# sousvide.net
KiCad netlist of a schematic drawn in EAGLE
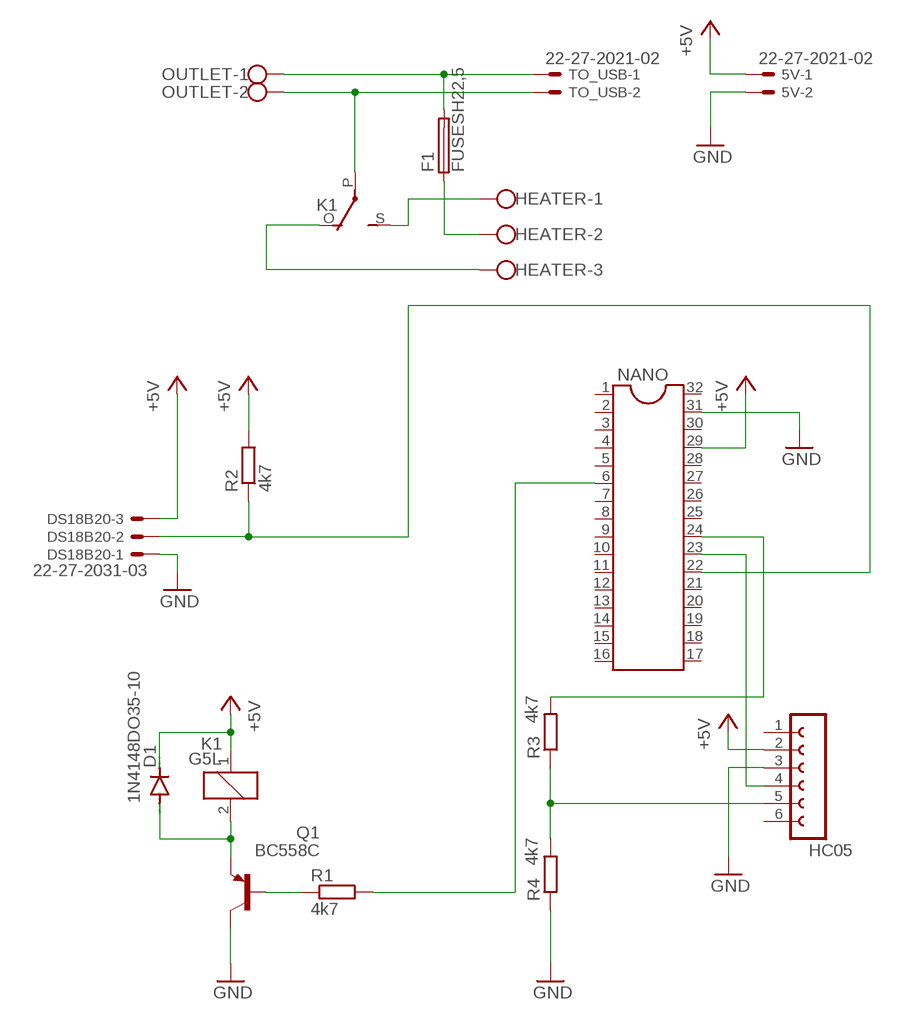
[diagram p0: schematic, sheet 1]

(export (version "E")
  (design (tool "Eeschema 10.0.6"))
  (components
    (comp (ref "5V")
      (value "22-27-2021-02")
      (footprint "eagle-import:6410-02")
      (fields (field (name "MF") "MOLEX"))
      (libsource (lib "eagle-import") (part "22-?-0227-2021"))
    )
    (comp (ref "D1")
      (value "1N4148DO35-10")
      (footprint "eagle-import:DO35-10")
      (libsource (lib "eagle-import") (part "1N4148DO35-10"))
    )
    (comp (ref "DS18B20")
      (value "22-27-2031-03")
      (footprint "eagle-import:6410-03")
      (fields (field (name "MF") "MOLEX"))
      (libsource (lib "eagle-import") (part "22-?-0327-2031"))
    )
    (comp (ref "F1")
      (value "FUSESH22,5")
      (footprint "eagle-import:SH22,5")
      (libsource (lib "eagle-import") (part "FUSESH22,5"))
    )
    (comp (ref "HC05")
      (value "FE06-1")
      (footprint "eagle-import:FE06")
      (libsource (lib "eagle-import") (part "FE06-1"))
    )
    (comp (ref "HEATER")
      (value "W237-103")
      (footprint "eagle-import:W237-103")
      (fields (field (name "MPN") "237-103"))
      (libsource (lib "eagle-import") (part "W237-103"))
    )
    (comp (ref "K1")
      (value "G5L")
      (footprint "eagle-import:G5LE")
      (libsource (lib "eagle-import") (part "G5L"))
    )
    (comp (ref "NANO")
      (value "DIL32")
      (footprint "eagle-import:DIL32")
      (libsource (lib "eagle-import") (part "DIL32"))
    )
    (comp (ref "OUTLET")
      (value "W237-102")
      (footprint "eagle-import:W237-102")
      (fields (field (name "MPN") "237-102"))
      (libsource (lib "eagle-import") (part "W237-102"))
    )
    (comp (ref "Q1")
      (value "BC558C")
      (footprint "eagle-import:TO92-EBC")
      (libsource (lib "eagle-import") (part "BC558C"))
    )
    (comp (ref "R1")
      (value "4k7")
      (footprint "eagle-import:0204_7")
      (libsource (lib "eagle-import") (part "R-EU_0204/7"))
    )
    (comp (ref "R2")
      (value "4k7")
      (footprint "eagle-import:0204_7")
      (libsource (lib "eagle-import") (part "R-EU_0204/7"))
    )
    (comp (ref "R3")
      (value "4k7")
      (footprint "eagle-import:0204_7")
      (libsource (lib "eagle-import") (part "R-EU_0204/7"))
    )
    (comp (ref "R4")
      (value "4k7")
      (footprint "eagle-import:0204_7")
      (libsource (lib "eagle-import") (part "R-EU_0204/7"))
    )
    (comp (ref "TO_USB")
      (value "22-27-2021-02")
      (footprint "eagle-import:6410-02")
      (fields (field (name "MF") "MOLEX"))
      (libsource (lib "eagle-import") (part "22-?-0227-2021"))
    )
  )
  (nets
    (net (code "1") (name "+5V") (class "Default")
      (node (ref "5V") (pin "1") (pinfunction "S_1") (pintype "passive"))
      (node (ref "D1") (pin "C") (pinfunction "C_C") (pintype "passive"))
      (node (ref "DS18B20") (pin "3") (pinfunction "S_3") (pintype "passive"))
      (node (ref "HC05") (pin "2") (pinfunction "2_2") (pintype "passive"))
      (node (ref "K1") (pin "1") (pinfunction "1_1") (pintype "passive"))
      (node (ref "NANO") (pin "29") (pinfunction "29_29") (pintype "passive"))
      (node (ref "R2") (pin "2") (pinfunction "2_2") (pintype "passive"))
    )
    (net (code "2") (name "GND") (class "Default")
      (node (ref "5V") (pin "2") (pinfunction "S_2") (pintype "passive"))
      (node (ref "DS18B20") (pin "1") (pinfunction "S_1") (pintype "passive"))
      (node (ref "HC05") (pin "3") (pinfunction "3_3") (pintype "passive"))
      (node (ref "NANO") (pin "31") (pinfunction "31_31") (pintype "passive"))
      (node (ref "Q1") (pin "C") (pinfunction "C_C") (pintype "passive"))
      (node (ref "R4") (pin "1") (pinfunction "1_1") (pintype "passive"))
    )
    (net (code "3") (name "Net-(D1-PadA)") (class "Default")
      (node (ref "D1") (pin "A") (pinfunction "A_A") (pintype "passive"))
      (node (ref "K1") (pin "2") (pinfunction "2_2") (pintype "passive"))
      (node (ref "Q1") (pin "E") (pinfunction "E_E") (pintype "passive"))
    )
    (net (code "4") (name "Net-(DS18B20B-S)") (class "Default")
      (node (ref "DS18B20") (pin "2") (pinfunction "S_2") (pintype "passive"))
      (node (ref "NANO") (pin "22") (pinfunction "22_22") (pintype "passive"))
      (node (ref "R2") (pin "1") (pinfunction "1_1") (pintype "passive"))
    )
    (net (code "5") (name "Net-(HC05-Pad4)") (class "Default")
      (node (ref "HC05") (pin "4") (pinfunction "4_4") (pintype "passive"))
      (node (ref "NANO") (pin "23") (pinfunction "23_23") (pintype "passive"))
    )
    (net (code "6") (name "Net-(HC05-Pad5)") (class "Default")
      (node (ref "HC05") (pin "5") (pinfunction "5_5") (pintype "passive"))
      (node (ref "R3") (pin "1") (pinfunction "1_1") (pintype "passive"))
      (node (ref "R4") (pin "2") (pinfunction "2_2") (pintype "passive"))
    )
    (net (code "7") (name "Net-(HEATERA-KL)") (class "Default")
      (node (ref "HEATER") (pin "1") (pinfunction "KL_1") (pintype "passive"))
      (node (ref "K1") (pin "S") (pinfunction "S_S") (pintype "passive"))
    )
    (net (code "8") (name "Net-(HEATERB-KL)") (class "Default")
      (node (ref "F1") (pin "1") (pinfunction "1_1") (pintype "passive"))
      (node (ref "HEATER") (pin "2") (pinfunction "KL_2") (pintype "passive"))
    )
    (net (code "9") (name "Net-(HEATERC-KL)") (class "Default")
      (node (ref "HEATER") (pin "3") (pinfunction "KL_3") (pintype "passive"))
      (node (ref "K1") (pin "O") (pinfunction "O_O") (pintype "passive"))
    )
    (net (code "10") (name "Net-(NANO-Pad6)") (class "Default")
      (node (ref "NANO") (pin "6") (pinfunction "6_6") (pintype "passive"))
      (node (ref "R1") (pin "2") (pinfunction "2_2") (pintype "passive"))
    )
    (net (code "11") (name "Net-(NANO-Pad24)") (class "Default")
      (node (ref "NANO") (pin "24") (pinfunction "24_24") (pintype "passive"))
      (node (ref "R3") (pin "2") (pinfunction "2_2") (pintype "passive"))
    )
    (net (code "12") (name "Net-(OUTLETA-KL)") (class "Default")
      (node (ref "F1") (pin "2") (pinfunction "2_2") (pintype "passive"))
      (node (ref "OUTLET") (pin "1") (pinfunction "KL_1") (pintype "passive"))
      (node (ref "TO_USB") (pin "1") (pinfunction "S_1") (pintype "passive"))
    )
    (net (code "13") (name "Net-(OUTLETB-KL)") (class "Default")
      (node (ref "K1") (pin "P") (pinfunction "P_P") (pintype "passive"))
      (node (ref "OUTLET") (pin "2") (pinfunction "KL_2") (pintype "passive"))
      (node (ref "TO_USB") (pin "2") (pinfunction "S_2") (pintype "passive"))
    )
    (net (code "14") (name "Net-(Q1-PadB)") (class "Default")
      (node (ref "Q1") (pin "B") (pinfunction "B_B") (pintype "passive"))
      (node (ref "R1") (pin "1") (pinfunction "1_1") (pintype "passive"))
    )
    (net (code "15") (name "unconnected-(HC05-Pad1)") (class "Default")
      (node (ref "HC05") (pin "1") (pinfunction "1_1") (pintype "passive"))
    )
    (net (code "16") (name "unconnected-(HC05-Pad6)") (class "Default")
      (node (ref "HC05") (pin "6") (pinfunction "6_6") (pintype "passive"))
    )
    (net (code "17") (name "unconnected-(NANO-Pad1)") (class "Default")
      (node (ref "NANO") (pin "1") (pinfunction "1_1") (pintype "passive"))
    )
    (net (code "18") (name "unconnected-(NANO-Pad2)") (class "Default")
      (node (ref "NANO") (pin "2") (pinfunction "2_2") (pintype "passive"))
    )
    (net (code "19") (name "unconnected-(NANO-Pad3)") (class "Default")
      (node (ref "NANO") (pin "3") (pinfunction "3_3") (pintype "passive"))
    )
    (net (code "20") (name "unconnected-(NANO-Pad4)") (class "Default")
      (node (ref "NANO") (pin "4") (pinfunction "4_4") (pintype "passive"))
    )
    (net (code "21") (name "unconnected-(NANO-Pad5)") (class "Default")
      (node (ref "NANO") (pin "5") (pinfunction "5_5") (pintype "passive"))
    )
    (net (code "22") (name "unconnected-(NANO-Pad7)") (class "Default")
      (node (ref "NANO") (pin "7") (pinfunction "7_7") (pintype "passive"))
    )
    (net (code "23") (name "unconnected-(NANO-Pad8)") (class "Default")
      (node (ref "NANO") (pin "8") (pinfunction "8_8") (pintype "passive"))
    )
    (net (code "24") (name "unconnected-(NANO-Pad9)") (class "Default")
      (node (ref "NANO") (pin "9") (pinfunction "9_9") (pintype "passive"))
    )
    (net (code "25") (name "unconnected-(NANO-Pad10)") (class "Default")
      (node (ref "NANO") (pin "10") (pinfunction "10_10") (pintype "passive"))
    )
    (net (code "26") (name "unconnected-(NANO-Pad11)") (class "Default")
      (node (ref "NANO") (pin "11") (pinfunction "11_11") (pintype "passive"))
    )
    (net (code "27") (name "unconnected-(NANO-Pad12)") (class "Default")
      (node (ref "NANO") (pin "12") (pinfunction "12_12") (pintype "passive"))
    )
    (net (code "28") (name "unconnected-(NANO-Pad13)") (class "Default")
      (node (ref "NANO") (pin "13") (pinfunction "13_13") (pintype "passive"))
    )
    (net (code "29") (name "unconnected-(NANO-Pad14)") (class "Default")
      (node (ref "NANO") (pin "14") (pinfunction "14_14") (pintype "passive"))
    )
    (net (code "30") (name "unconnected-(NANO-Pad15)") (class "Default")
      (node (ref "NANO") (pin "15") (pinfunction "15_15") (pintype "passive"))
    )
    (net (code "31") (name "unconnected-(NANO-Pad16)") (class "Default")
      (node (ref "NANO") (pin "16") (pinfunction "16_16") (pintype "passive"))
    )
    (net (code "32") (name "unconnected-(NANO-Pad17)") (class "Default")
      (node (ref "NANO") (pin "17") (pinfunction "17_17") (pintype "passive"))
    )
    (net (code "33") (name "unconnected-(NANO-Pad18)") (class "Default")
      (node (ref "NANO") (pin "18") (pinfunction "18_18") (pintype "passive"))
    )
    (net (code "34") (name "unconnected-(NANO-Pad19)") (class "Default")
      (node (ref "NANO") (pin "19") (pinfunction "19_19") (pintype "passive"))
    )
    (net (code "35") (name "unconnected-(NANO-Pad20)") (class "Default")
      (node (ref "NANO") (pin "20") (pinfunction "20_20") (pintype "passive"))
    )
    (net (code "36") (name "unconnected-(NANO-Pad21)") (class "Default")
      (node (ref "NANO") (pin "21") (pinfunction "21_21") (pintype "passive"))
    )
    (net (code "37") (name "unconnected-(NANO-Pad25)") (class "Default")
      (node (ref "NANO") (pin "25") (pinfunction "25_25") (pintype "passive"))
    )
    (net (code "38") (name "unconnected-(NANO-Pad26)") (class "Default")
      (node (ref "NANO") (pin "26") (pinfunction "26_26") (pintype "passive"))
    )
    (net (code "39") (name "unconnected-(NANO-Pad27)") (class "Default")
      (node (ref "NANO") (pin "27") (pinfunction "27_27") (pintype "passive"))
    )
    (net (code "40") (name "unconnected-(NANO-Pad28)") (class "Default")
      (node (ref "NANO") (pin "28") (pinfunction "28_28") (pintype "passive"))
    )
    (net (code "41") (name "unconnected-(NANO-Pad30)") (class "Default")
      (node (ref "NANO") (pin "30") (pinfunction "30_30") (pintype "passive"))
    )
    (net (code "42") (name "unconnected-(NANO-Pad32)") (class "Default")
      (node (ref "NANO") (pin "32") (pinfunction "32_32") (pintype "passive"))
    )
  )
)
